# Receiver.net
KiCad netlist of a schematic drawn in EAGLE
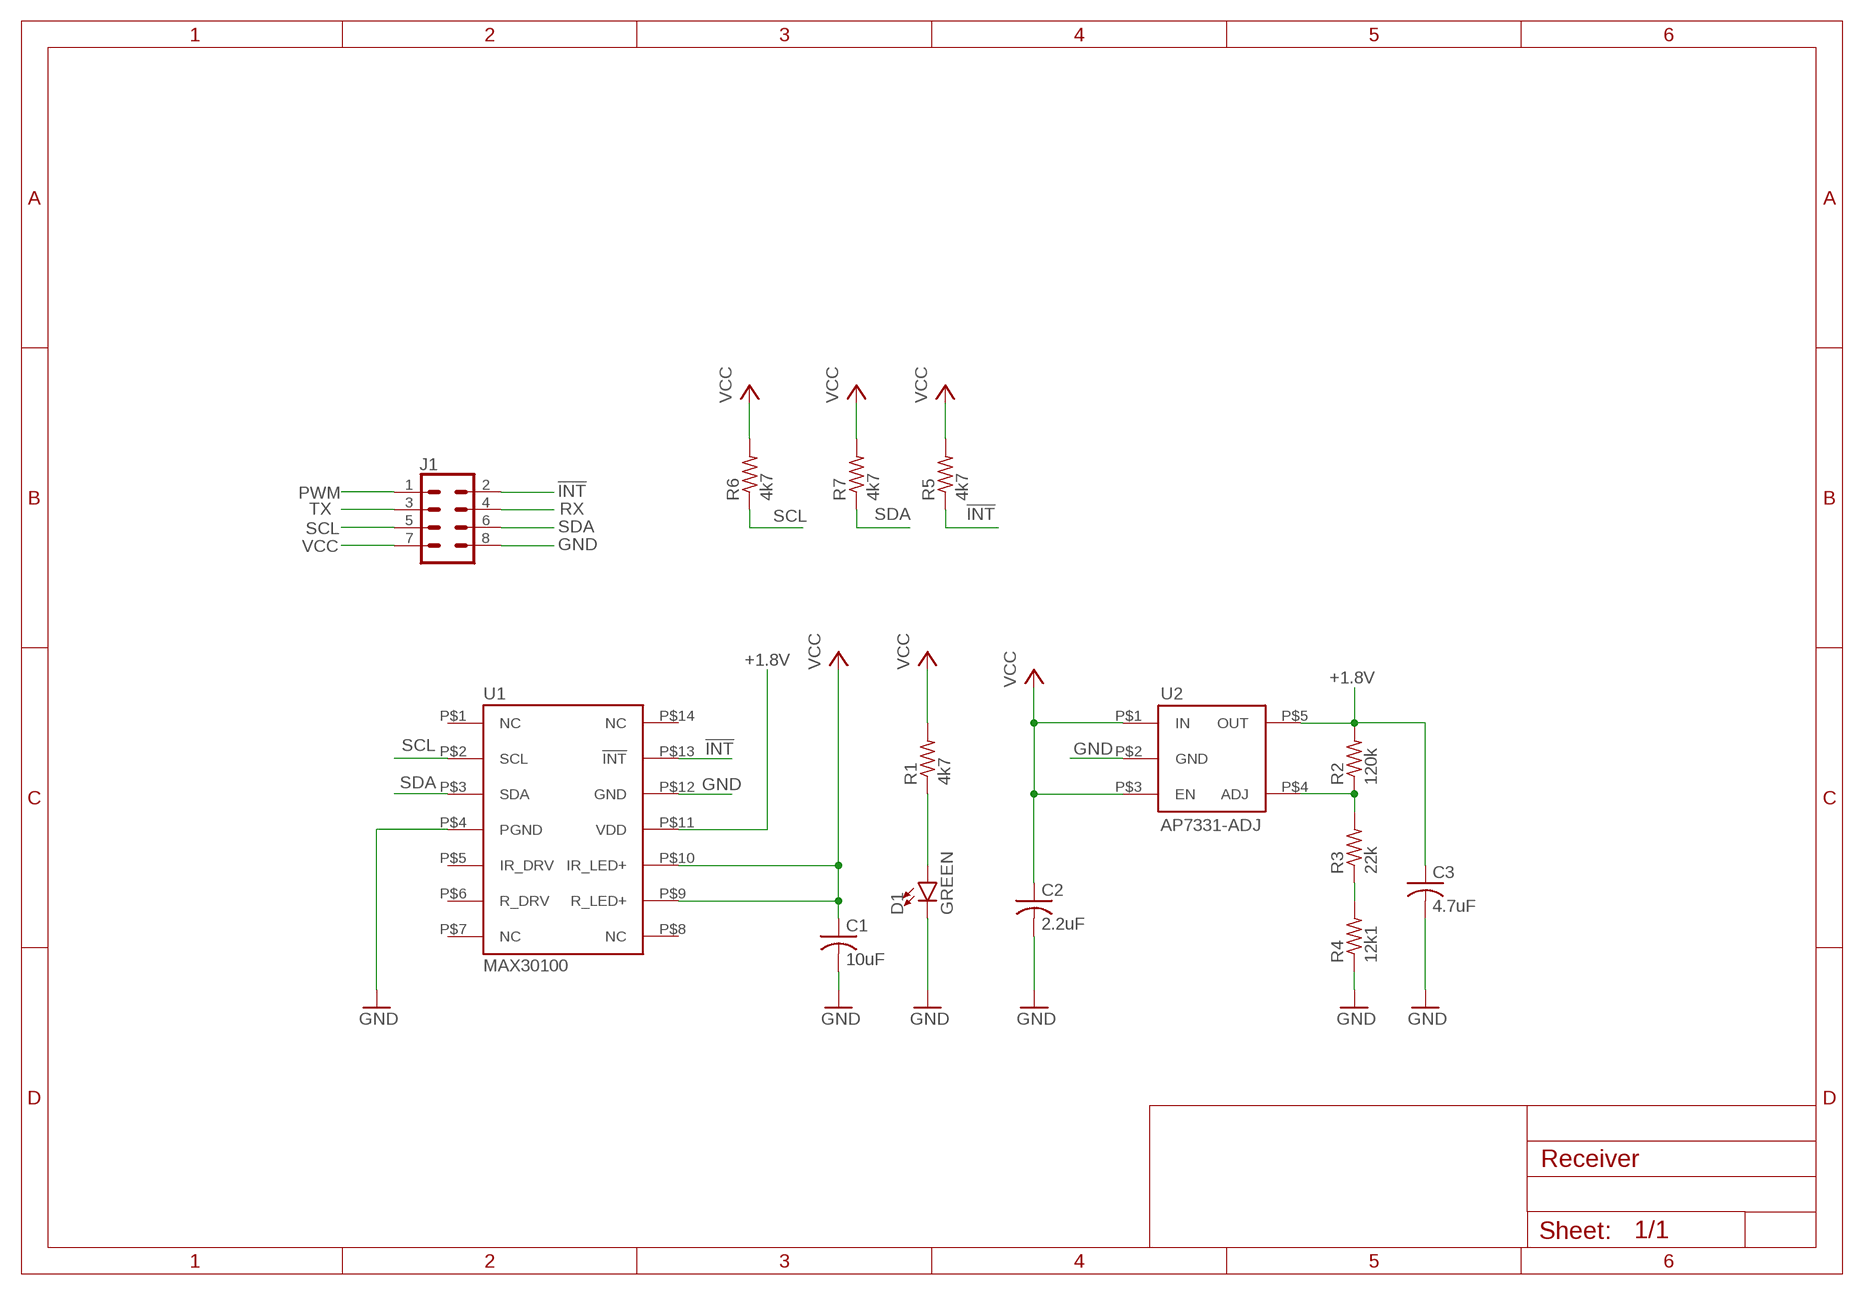
[diagram p0: schematic, sheet 1]

(export (version "E")
  (design (tool "Eeschema 10.0.6"))
  (components
    (comp (ref "C1")
      (value "10uF")
      (footprint "eagle-import:C0805")
      (libsource (lib "eagle-import") (part "C-USC0805"))
    )
    (comp (ref "C2")
      (value "2.2uF")
      (footprint "eagle-import:C0805")
      (libsource (lib "eagle-import") (part "C-USC0805"))
    )
    (comp (ref "C3")
      (value "4.7uF")
      (footprint "eagle-import:C0805")
      (libsource (lib "eagle-import") (part "C-USC0805"))
    )
    (comp (ref "D1")
      (value "GREEN")
      (footprint "eagle-import:LED-0603")
      (libsource (lib "eagle-import") (part "LED-GREEN0603"))
    )
    (comp (ref "J1")
      (value "CONN_04X2")
      (footprint "eagle-import:2X4")
      (libsource (lib "eagle-import") (part "CONN_04X2"))
    )
    (comp (ref "R1")
      (value "4k7")
      (footprint "eagle-import:R0805")
      (libsource (lib "eagle-import") (part "R-US_R0805"))
    )
    (comp (ref "R2")
      (value "120k")
      (footprint "eagle-import:R0805")
      (libsource (lib "eagle-import") (part "R-US_R0805"))
    )
    (comp (ref "R3")
      (value "22k")
      (footprint "eagle-import:R0805")
      (libsource (lib "eagle-import") (part "R-US_R0805"))
    )
    (comp (ref "R4")
      (value "12k1")
      (footprint "eagle-import:R0805")
      (libsource (lib "eagle-import") (part "R-US_R0805"))
    )
    (comp (ref "R5")
      (value "4k7")
      (footprint "eagle-import:R0805")
      (libsource (lib "eagle-import") (part "R-US_R0805"))
    )
    (comp (ref "R6")
      (value "4k7")
      (footprint "eagle-import:R0805")
      (libsource (lib "eagle-import") (part "R-US_R0805"))
    )
    (comp (ref "R7")
      (value "4k7")
      (footprint "eagle-import:R0805")
      (libsource (lib "eagle-import") (part "R-US_R0805"))
    )
    (comp (ref "U1")
      (value "MAX30100")
      (footprint "eagle-import:14OESIP")
      (libsource (lib "eagle-import") (part "MAX30100"))
    )
    (comp (ref "U2")
      (value "AP7331-ADJ")
      (footprint "eagle-import:SOT25")
      (libsource (lib "eagle-import") (part "AP7331-ADJ"))
    )
  )
  (nets
    (net (code "1") (name "/+1.8V") (class "Default")
      (node (ref "C3") (pin "1") (pinfunction "1_1") (pintype "passive"))
      (node (ref "R2") (pin "2") (pinfunction "2_2") (pintype "passive"))
      (node (ref "U1") (pin "P$11") (pinfunction "VDD_P$11") (pintype "bidirectional"))
      (node (ref "U2") (pin "P$5") (pinfunction "OUT_P$5") (pintype "bidirectional"))
    )
    (net (code "2") (name "/PWM") (class "Default")
      (node (ref "J1") (pin "1") (pinfunction "1_1") (pintype "passive"))
    )
    (net (code "3") (name "/RX") (class "Default")
      (node (ref "J1") (pin "4") (pinfunction "4_4") (pintype "passive"))
    )
    (net (code "4") (name "/SCL") (class "Default")
      (node (ref "J1") (pin "5") (pinfunction "5_5") (pintype "passive"))
      (node (ref "R6") (pin "1") (pinfunction "1_1") (pintype "passive"))
      (node (ref "U1") (pin "P$2") (pinfunction "SCL_P$2") (pintype "bidirectional"))
    )
    (net (code "5") (name "/SDA") (class "Default")
      (node (ref "J1") (pin "6") (pinfunction "6_6") (pintype "passive"))
      (node (ref "R7") (pin "1") (pinfunction "1_1") (pintype "passive"))
      (node (ref "U1") (pin "P$3") (pinfunction "SDA_P$3") (pintype "bidirectional"))
    )
    (net (code "6") (name "/TX") (class "Default")
      (node (ref "J1") (pin "3") (pinfunction "3_3") (pintype "passive"))
    )
    (net (code "7") (name "/~{INT}") (class "Default")
      (node (ref "J1") (pin "2") (pinfunction "2_2") (pintype "passive"))
      (node (ref "R5") (pin "1") (pinfunction "1_1") (pintype "passive"))
      (node (ref "U1") (pin "P$13") (pinfunction "~{INT}_P$13") (pintype "bidirectional"))
    )
    (net (code "8") (name "GND") (class "Default")
      (node (ref "C1") (pin "2") (pinfunction "2_2") (pintype "passive"))
      (node (ref "C2") (pin "2") (pinfunction "2_2") (pintype "passive"))
      (node (ref "C3") (pin "2") (pinfunction "2_2") (pintype "passive"))
      (node (ref "D1") (pin "C") (pinfunction "C_C") (pintype "passive"))
      (node (ref "J1") (pin "8") (pinfunction "8_8") (pintype "passive"))
      (node (ref "R4") (pin "1") (pinfunction "1_1") (pintype "passive"))
      (node (ref "U1") (pin "P$12") (pinfunction "GND_P$12") (pintype "bidirectional"))
      (node (ref "U1") (pin "P$4") (pinfunction "PGND_P$4") (pintype "bidirectional"))
      (node (ref "U2") (pin "P$2") (pinfunction "GND_P$2") (pintype "bidirectional"))
    )
    (net (code "9") (name "Net-(D1-PadA)") (class "Default")
      (node (ref "D1") (pin "A") (pinfunction "A_A") (pintype "passive"))
      (node (ref "R1") (pin "1") (pinfunction "1_1") (pintype "passive"))
    )
    (net (code "10") (name "Net-(R3-Pad1)") (class "Default")
      (node (ref "R3") (pin "1") (pinfunction "1_1") (pintype "passive"))
      (node (ref "R4") (pin "2") (pinfunction "2_2") (pintype "passive"))
    )
    (net (code "11") (name "Net-(U2-ADJ)") (class "Default")
      (node (ref "R2") (pin "1") (pinfunction "1_1") (pintype "passive"))
      (node (ref "R3") (pin "2") (pinfunction "2_2") (pintype "passive"))
      (node (ref "U2") (pin "P$4") (pinfunction "ADJ_P$4") (pintype "bidirectional"))
    )
    (net (code "12") (name "VCC") (class "Default")
      (node (ref "C1") (pin "1") (pinfunction "1_1") (pintype "passive"))
      (node (ref "C2") (pin "1") (pinfunction "1_1") (pintype "passive"))
      (node (ref "J1") (pin "7") (pinfunction "7_7") (pintype "passive"))
      (node (ref "R1") (pin "2") (pinfunction "2_2") (pintype "passive"))
      (node (ref "R5") (pin "2") (pinfunction "2_2") (pintype "passive"))
      (node (ref "R6") (pin "2") (pinfunction "2_2") (pintype "passive"))
      (node (ref "R7") (pin "2") (pinfunction "2_2") (pintype "passive"))
      (node (ref "U1") (pin "P$10") (pinfunction "IR_LED+_P$10") (pintype "bidirectional"))
      (node (ref "U1") (pin "P$9") (pinfunction "R_LED+_P$9") (pintype "bidirectional"))
      (node (ref "U2") (pin "P$1") (pinfunction "IN_P$1") (pintype "bidirectional"))
      (node (ref "U2") (pin "P$3") (pinfunction "EN_P$3") (pintype "bidirectional"))
    )
    (net (code "13") (name "unconnected-(U1-IR_DRV-PadP$5)") (class "Default")
      (node (ref "U1") (pin "P$5") (pinfunction "IR_DRV_P$5") (pintype "bidirectional"))
    )
    (net (code "14") (name "unconnected-(U1-NC-PadP$1)") (class "Default")
      (node (ref "U1") (pin "P$1") (pinfunction "NC_P$1") (pintype "bidirectional"))
    )
    (net (code "15") (name "unconnected-(U1-NC-PadP$7)") (class "Default")
      (node (ref "U1") (pin "P$7") (pinfunction "NC_P$7") (pintype "bidirectional"))
    )
    (net (code "16") (name "unconnected-(U1-NC-PadP$8)") (class "Default")
      (node (ref "U1") (pin "P$8") (pinfunction "NC_P$8") (pintype "bidirectional"))
    )
    (net (code "17") (name "unconnected-(U1-NC-PadP$14)") (class "Default")
      (node (ref "U1") (pin "P$14") (pinfunction "NC_P$14") (pintype "bidirectional"))
    )
    (net (code "18") (name "unconnected-(U1-R_DRV-PadP$6)") (class "Default")
      (node (ref "U1") (pin "P$6") (pinfunction "R_DRV_P$6") (pintype "bidirectional"))
    )
  )
)
